# audio_tas5720_amplifier.net
KiCad netlist of a schematic drawn in Altium Designer
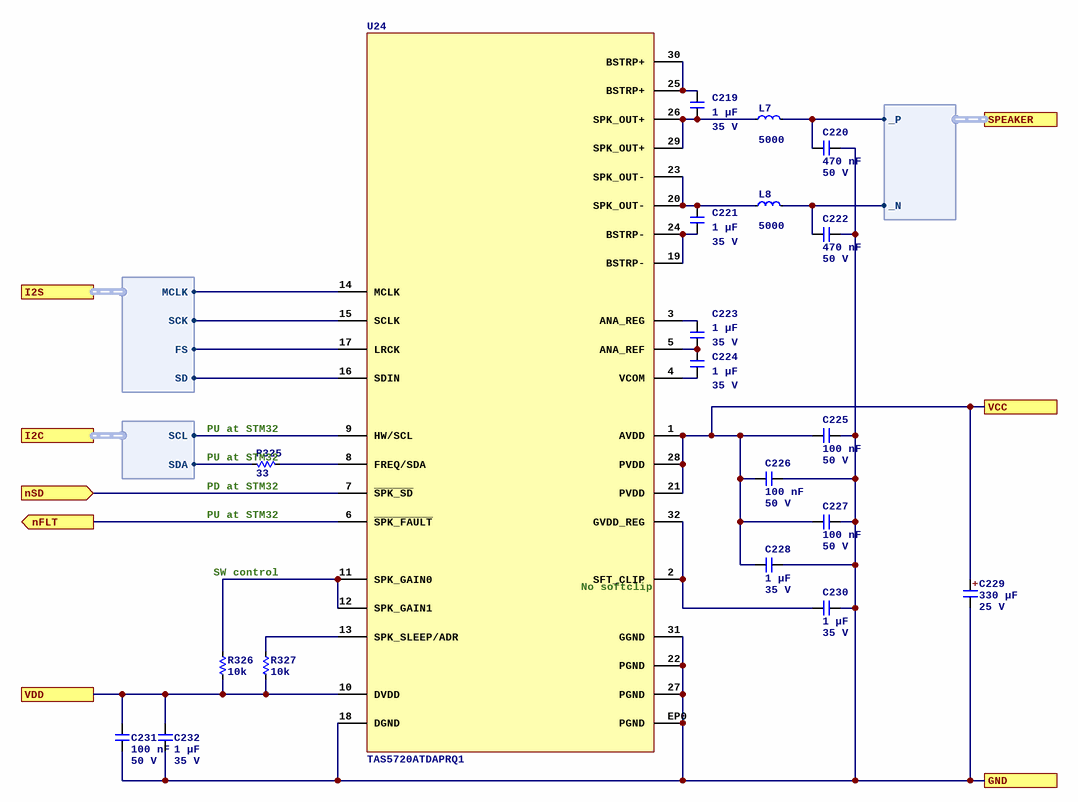
[diagram p0: audio_tas5720_amplifier.SchDoc]

(export (version "E")
  (design (tool "Eeschema 10.0.6"))
  (components
    (comp (ref "C219")
      (value "GMK107AB7105KAHT")
      (footprint "C0603")
      (fields
        (field (name "CAPACITANCE") "1 µF")
        (field (name "MANUFACTURER") "Taiyo Yuden")
        (field (name "VOLTAGE RATING") "35 V")
      )
      (libsource (lib "database") (part "__template_cap"))
    )
    (comp (ref "C220")
      (value "CC0603KRX7R9BB474")
      (footprint "C0603")
      (fields
        (field (name "CAPACITANCE") "470 nF")
        (field (name "MANUFACTURER") "YAGEO")
        (field (name "VOLTAGE RATING") "50 V")
      )
      (libsource (lib "database") (part "__template_cap"))
    )
    (comp (ref "C221")
      (value "GMK107AB7105KAHT")
      (footprint "C0603")
      (fields
        (field (name "CAPACITANCE") "1 µF")
        (field (name "MANUFACTURER") "Taiyo Yuden")
        (field (name "VOLTAGE RATING") "35 V")
      )
      (libsource (lib "database") (part "__template_cap"))
    )
    (comp (ref "C222")
      (value "CC0603KRX7R9BB474")
      (footprint "C0603")
      (fields
        (field (name "CAPACITANCE") "470 nF")
        (field (name "MANUFACTURER") "YAGEO")
        (field (name "VOLTAGE RATING") "50 V")
      )
      (libsource (lib "database") (part "__template_cap"))
    )
    (comp (ref "C223")
      (value "GMK107AB7105KAHT")
      (footprint "C0603")
      (fields
        (field (name "CAPACITANCE") "1 µF")
        (field (name "MANUFACTURER") "Taiyo Yuden")
        (field (name "VOLTAGE RATING") "35 V")
      )
      (libsource (lib "database") (part "__template_cap"))
    )
    (comp (ref "C224")
      (value "GMK107AB7105KAHT")
      (footprint "C0603")
      (fields
        (field (name "CAPACITANCE") "1 µF")
        (field (name "MANUFACTURER") "Taiyo Yuden")
        (field (name "VOLTAGE RATING") "35 V")
      )
      (libsource (lib "database") (part "__template_cap"))
    )
    (comp (ref "C225")
      (value "CL05B104KB54PNC")
      (footprint "C0402")
      (fields
        (field (name "CAPACITANCE") "100 nF")
        (field (name "MANUFACTURER") "Samsung Electro-Mechanics")
        (field (name "VOLTAGE RATING") "50 V")
      )
      (libsource (lib "database") (part "__template_cap"))
    )
    (comp (ref "C226")
      (value "CL05B104KB54PNC")
      (footprint "C0402")
      (fields
        (field (name "CAPACITANCE") "100 nF")
        (field (name "MANUFACTURER") "Samsung Electro-Mechanics")
        (field (name "VOLTAGE RATING") "50 V")
      )
      (libsource (lib "database") (part "__template_cap"))
    )
    (comp (ref "C227")
      (value "CL05B104KB54PNC")
      (footprint "C0402")
      (fields
        (field (name "CAPACITANCE") "100 nF")
        (field (name "MANUFACTURER") "Samsung Electro-Mechanics")
        (field (name "VOLTAGE RATING") "50 V")
      )
      (libsource (lib "database") (part "__template_cap"))
    )
    (comp (ref "C228")
      (value "GMK107AB7105KAHT")
      (footprint "C0603")
      (fields
        (field (name "CAPACITANCE") "1 µF")
        (field (name "MANUFACTURER") "Taiyo Yuden")
        (field (name "VOLTAGE RATING") "35 V")
      )
      (libsource (lib "database") (part "__template_cap"))
    )
    (comp (ref "C229")
      (value "EEH-ZC1E331P")
      (footprint "CAP_10001050_SMD")
      (description "SMD hybrid aluminum polymer capacitor, 330 µF, 25 V")
      (fields
        (field (name "MANUFACTURER") "Panasonic Industry")
        (field (name "CAPACITANCE") "330 µF")
        (field (name "VOLTAGE RATING") "25 V")
      )
      (libsource (lib "database") (part "__template_cap_p"))
    )
    (comp (ref "C230")
      (value "GMK107AB7105KAHT")
      (footprint "C0603")
      (fields
        (field (name "CAPACITANCE") "1 µF")
        (field (name "MANUFACTURER") "Taiyo Yuden")
        (field (name "VOLTAGE RATING") "35 V")
      )
      (libsource (lib "database") (part "__template_cap"))
    )
    (comp (ref "C231")
      (value "CL05B104KB54PNC")
      (footprint "C0402")
      (fields
        (field (name "CAPACITANCE") "100 nF")
        (field (name "MANUFACTURER") "Samsung Electro-Mechanics")
        (field (name "VOLTAGE RATING") "50 V")
      )
      (libsource (lib "database") (part "__template_cap"))
    )
    (comp (ref "C232")
      (value "GMK107AB7105KAHT")
      (footprint "C0603")
      (fields
        (field (name "CAPACITANCE") "1 µF")
        (field (name "MANUFACTURER") "Taiyo Yuden")
        (field (name "VOLTAGE RATING") "35 V")
      )
      (libsource (lib "database") (part "__template_cap"))
    )
    (comp (ref "L7")
      (value "SRP5050FA-100M1")
      (footprint "BOURNS_SRP5050FA")
      (description "10 µH shielded power inductor")
      (fields (field (name "MANUFACTURER") "BOURNS") (field (name "CURRENT RATING (MA)") "5000"))
      (libsource (lib "database") (part "__template_inductor"))
    )
    (comp (ref "L8")
      (value "SRP5050FA-100M1")
      (footprint "BOURNS_SRP5050FA")
      (description "10 µH shielded power inductor")
      (fields (field (name "MANUFACTURER") "BOURNS") (field (name "CURRENT RATING (MA)") "5000"))
      (libsource (lib "database") (part "__template_inductor"))
    )
    (comp (ref "R325")
      (value "33")
      (footprint "R0402")
      (fields
        (field (name "TOLERANCE") "1%")
        (field (name "MANUFACTURER PART NUMBER") "0402WGF330JTCE")
        (field (name "MANUFACTURER") "UNI-ROYAL(Uniroyal Elec)")
      )
      (libsource (lib "database") (part "__template_resistor"))
    )
    (comp (ref "R326")
      (value "10k")
      (footprint "R0402")
      (fields
        (field (name "MANUFACTURER PART NUMBER") "0402WGF1002TCE")
        (field (name "MANUFACTURER") "UNI-ROYAL(Uniroyal Elec)")
        (field (name "TOLERANCE") "1%")
      )
      (libsource (lib "database") (part "__template_resistor"))
    )
    (comp (ref "R327")
      (value "10k")
      (footprint "R0402")
      (fields
        (field (name "MANUFACTURER PART NUMBER") "0402WGF1002TCE")
        (field (name "MANUFACTURER") "UNI-ROYAL(Uniroyal Elec)")
        (field (name "TOLERANCE") "1%")
      )
      (libsource (lib "database") (part "__template_resistor"))
    )
    (comp (ref "U24")
      (value "TAS5720ATDAPRQ1")
      (footprint "TI_DAP0032B")
      (description "Amplifier IC 1-Channel (Mono) Class D 32-HTSSOP")
      (fields (field (name "MANUFACTURER") "Texas Instruments"))
      (libsource (lib "database") (part "TAS5720ATDAPRQ1"))
    )
  )
  (nets
    (net (code "4") (name "/FS") (class "Default")
      (node (ref "U24") (pin "17") (pinfunction "LRCK_17") (pintype "passive"))
    )
    (net (code "5") (name "/GND") (class "Default")
      (node (ref "C220") (pin "2") (pintype "passive"))
      (node (ref "C222") (pin "2") (pintype "passive"))
      (node (ref "C225") (pin "2") (pintype "passive"))
      (node (ref "C226") (pin "2") (pintype "passive"))
      (node (ref "C227") (pin "2") (pintype "passive"))
      (node (ref "C228") (pin "2") (pintype "passive"))
      (node (ref "C229") (pin "2") (pintype "passive"))
      (node (ref "C230") (pin "2") (pintype "passive"))
      (node (ref "C231") (pin "2") (pintype "passive"))
      (node (ref "C232") (pin "2") (pintype "passive"))
      (node (ref "U24") (pin "18") (pinfunction "DGND_18") (pintype "passive"))
      (node (ref "U24") (pin "22") (pinfunction "PGND_22") (pintype "passive"))
      (node (ref "U24") (pin "27") (pinfunction "PGND_27") (pintype "passive"))
      (node (ref "U24") (pin "31") (pinfunction "GGND_31") (pintype "passive"))
      (node (ref "U24") (pin "EP0") (pinfunction "PGND_EP0") (pintype "passive"))
    )
    (net (code "6") (name "/MCLK") (class "Default")
      (node (ref "U24") (pin "14") (pinfunction "MCLK_14") (pintype "passive"))
    )
    (net (code "7") (name "/SCK") (class "Default")
      (node (ref "U24") (pin "15") (pinfunction "SCLK_15") (pintype "passive"))
    )
    (net (code "8") (name "/SCL") (class "Default")
      (node (ref "U24") (pin "9") (pinfunction "HW/SCL_9") (pintype "passive"))
    )
    (net (code "9") (name "/SD") (class "Default")
      (node (ref "U24") (pin "16") (pinfunction "SDIN_16") (pintype "passive"))
    )
    (net (code "10") (name "/SDA") (class "Default") (node (ref "R325") (pin "1") (pintype "passive")))
    (net (code "11") (name "/VCC") (class "Default")
      (node (ref "C225") (pin "1") (pintype "passive"))
      (node (ref "C226") (pin "1") (pintype "passive"))
      (node (ref "C227") (pin "1") (pintype "passive"))
      (node (ref "C228") (pin "1") (pintype "passive"))
      (node (ref "C229") (pin "1") (pintype "passive"))
      (node (ref "U24") (pin "1") (pinfunction "AVDD_1") (pintype "passive"))
      (node (ref "U24") (pin "21") (pinfunction "PVDD_21") (pintype "passive"))
      (node (ref "U24") (pin "28") (pinfunction "PVDD_28") (pintype "passive"))
    )
    (net (code "12") (name "/VDD") (class "Default")
      (node (ref "C231") (pin "1") (pintype "passive"))
      (node (ref "C232") (pin "1") (pintype "passive"))
      (node (ref "R326") (pin "2") (pintype "passive"))
      (node (ref "R327") (pin "2") (pintype "passive"))
      (node (ref "U24") (pin "10") (pinfunction "DVDD_10") (pintype "passive"))
    )
    (net (code "13") (name "/_N") (class "Default")
      (node (ref "C222") (pin "1") (pintype "passive"))
      (node (ref "L8") (pin "2") (pintype "passive"))
    )
    (net (code "14") (name "/_P") (class "Default")
      (node (ref "C220") (pin "1") (pintype "passive"))
      (node (ref "L7") (pin "2") (pintype "passive"))
    )
    (net (code "15") (name "/nFLT") (class "Default")
      (node (ref "U24") (pin "6") (pinfunction "~{SPK_FAULT}_6") (pintype "passive"))
    )
    (net (code "16") (name "/nSD") (class "Default")
      (node (ref "U24") (pin "7") (pinfunction "~{SPK_SD}_7") (pintype "passive"))
    )
    (net (code "20") (name "Net-(C219-Pad1)") (class "Default")
      (node (ref "C219") (pin "1") (pintype "passive"))
      (node (ref "U24") (pin "25") (pinfunction "BSTRP+_25") (pintype "passive"))
      (node (ref "U24") (pin "30") (pinfunction "BSTRP+_30") (pintype "passive"))
    )
    (net (code "21") (name "Net-(C219-Pad2)") (class "Default")
      (node (ref "C219") (pin "2") (pintype "passive"))
      (node (ref "L7") (pin "1") (pintype "passive"))
      (node (ref "U24") (pin "26") (pinfunction "SPK_OUT+_26") (pintype "passive"))
      (node (ref "U24") (pin "29") (pinfunction "SPK_OUT+_29") (pintype "passive"))
    )
    (net (code "22") (name "Net-(C221-Pad1)") (class "Default")
      (node (ref "C221") (pin "1") (pintype "passive"))
      (node (ref "L8") (pin "1") (pintype "passive"))
      (node (ref "U24") (pin "20") (pinfunction "SPK_OUT-_20") (pintype "passive"))
      (node (ref "U24") (pin "23") (pinfunction "SPK_OUT-_23") (pintype "passive"))
    )
    (net (code "23") (name "Net-(C221-Pad2)") (class "Default")
      (node (ref "C221") (pin "2") (pintype "passive"))
      (node (ref "U24") (pin "19") (pinfunction "BSTRP-_19") (pintype "passive"))
      (node (ref "U24") (pin "24") (pinfunction "BSTRP-_24") (pintype "passive"))
    )
    (net (code "24") (name "Net-(U24-ANA_REF)") (class "Default")
      (node (ref "C223") (pin "2") (pintype "passive"))
      (node (ref "C224") (pin "1") (pintype "passive"))
      (node (ref "U24") (pin "5") (pinfunction "ANA_REF_5") (pintype "passive"))
    )
    (net (code "25") (name "Net-(U24-ANA_REG)") (class "Default")
      (node (ref "C223") (pin "1") (pintype "passive"))
      (node (ref "U24") (pin "3") (pinfunction "ANA_REG_3") (pintype "passive"))
    )
    (net (code "26") (name "Net-(U24-FREQ{slash}SDA)") (class "Default")
      (node (ref "R325") (pin "2") (pintype "passive"))
      (node (ref "U24") (pin "8") (pinfunction "FREQ/SDA_8") (pintype "passive"))
    )
    (net (code "27") (name "Net-(U24-GVDD_REG)") (class "Default")
      (node (ref "C230") (pin "1") (pintype "passive"))
      (node (ref "U24") (pin "2") (pinfunction "SFT_CLIP_2") (pintype "passive"))
      (node (ref "U24") (pin "32") (pinfunction "GVDD_REG_32") (pintype "passive"))
    )
    (net (code "28") (name "Net-(U24-SPK_GAIN0)") (class "Default")
      (node (ref "R326") (pin "1") (pintype "passive"))
      (node (ref "U24") (pin "11") (pinfunction "SPK_GAIN0_11") (pintype "passive"))
      (node (ref "U24") (pin "12") (pinfunction "SPK_GAIN1_12") (pintype "passive"))
    )
    (net (code "29") (name "Net-(U24-SPK_SLEEP{slash}ADR)") (class "Default")
      (node (ref "R327") (pin "1") (pintype "passive"))
      (node (ref "U24") (pin "13") (pinfunction "SPK_SLEEP/ADR_13") (pintype "passive"))
    )
    (net (code "30") (name "Net-(U24-VCOM)") (class "Default")
      (node (ref "C224") (pin "2") (pintype "passive"))
      (node (ref "U24") (pin "4") (pinfunction "VCOM_4") (pintype "passive"))
    )
  )
)
